# dmx2uart.net
KiCad netlist of a schematic drawn in EAGLE
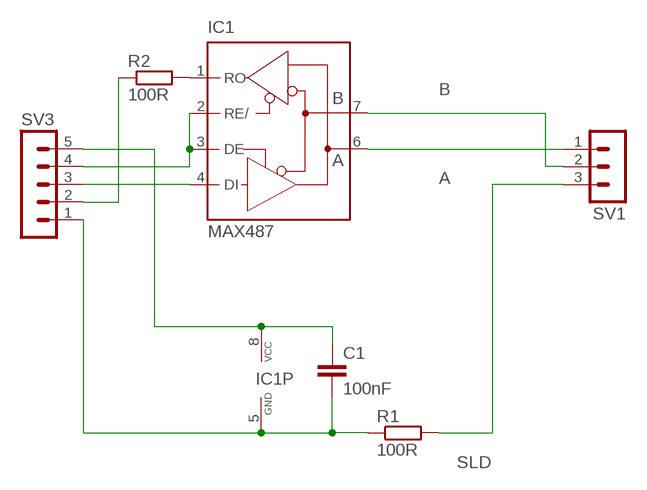
[diagram p0: schematic, sheet 1]

(export (version "E")
  (design (tool "Eeschema 10.0.6"))
  (components
    (comp (ref "C1")
      (value "100nF")
      (footprint "eagle-import:C075-032X103")
      (libsource (lib "eagle-import") (part "C-EU075-032X103"))
    )
    (comp (ref "IC1")
      (value "MAX487")
      (footprint "eagle-import:DIL08")
      (fields (field (name "MPN") "MAX481CPA+"))
      (libsource (lib "eagle-import") (part "MAX481CPA"))
    )
    (comp (ref "R1")
      (value "100R")
      (footprint "eagle-import:0207_7")
      (libsource (lib "eagle-import") (part "R-EU_0207/7"))
    )
    (comp (ref "R2")
      (value "100R")
      (footprint "eagle-import:0207_10")
      (libsource (lib "eagle-import") (part "resistor_R-EU_0207/10"))
    )
    (comp (ref "SV1")
      (value "MA03-1")
      (footprint "eagle-import:MA03-1")
      (libsource (lib "eagle-import") (part "MA03-1"))
    )
    (comp (ref "SV3")
      (value "MA05-1")
      (footprint "eagle-import:MA05-1")
      (libsource (lib "eagle-import") (part "MA05-1"))
    )
  )
  (nets
    (net (code "1") (name "/A") (class "Default")
      (node (ref "IC1") (pin "6") (pinfunction "A_6") (pintype "passive"))
      (node (ref "SV1") (pin "1") (pinfunction "1_1") (pintype "passive"))
    )
    (net (code "2") (name "/B") (class "Default")
      (node (ref "IC1") (pin "7") (pinfunction "B_7") (pintype "passive"))
      (node (ref "SV1") (pin "2") (pinfunction "2_2") (pintype "passive"))
    )
    (net (code "3") (name "/SLD") (class "Default")
      (node (ref "R1") (pin "2") (pinfunction "2_2") (pintype "passive"))
      (node (ref "SV1") (pin "3") (pinfunction "3_3") (pintype "passive"))
    )
    (net (code "4") (name "Net-(IC1A-DE)") (class "Default")
      (node (ref "IC1") (pin "2") (pinfunction "RE/_2") (pintype "input"))
      (node (ref "IC1") (pin "3") (pinfunction "DE_3") (pintype "input"))
      (node (ref "SV3") (pin "4") (pinfunction "4_4") (pintype "passive"))
    )
    (net (code "5") (name "Net-(IC1A-DI)") (class "Default")
      (node (ref "IC1") (pin "4") (pinfunction "DI_4") (pintype "input"))
      (node (ref "SV3") (pin "3") (pinfunction "3_3") (pintype "passive"))
    )
    (net (code "6") (name "Net-(IC1A-RO)") (class "Default")
      (node (ref "IC1") (pin "1") (pinfunction "RO_1") (pintype "output"))
      (node (ref "R2") (pin "2") (pinfunction "2_2") (pintype "passive"))
    )
    (net (code "7") (name "Net-(IC1B-GND)") (class "Default")
      (node (ref "C1") (pin "2") (pinfunction "2_2") (pintype "passive"))
      (node (ref "IC1") (pin "5") (pinfunction "GND_5") (pintype "power_in"))
      (node (ref "R1") (pin "1") (pinfunction "1_1") (pintype "passive"))
      (node (ref "SV3") (pin "1") (pinfunction "1_1") (pintype "passive"))
    )
    (net (code "8") (name "Net-(IC1B-VCC)") (class "Default")
      (node (ref "C1") (pin "1") (pinfunction "1_1") (pintype "passive"))
      (node (ref "IC1") (pin "8") (pinfunction "VCC_8") (pintype "power_in"))
      (node (ref "SV3") (pin "5") (pinfunction "5_5") (pintype "passive"))
    )
    (net (code "9") (name "Net-(R2-Pad1)") (class "Default")
      (node (ref "R2") (pin "1") (pinfunction "1_1") (pintype "passive"))
      (node (ref "SV3") (pin "2") (pinfunction "2_2") (pintype "passive"))
    )
  )
)
